# Headers-SolderPads.net
KiCad netlist of a schematic drawn in Altium Designer
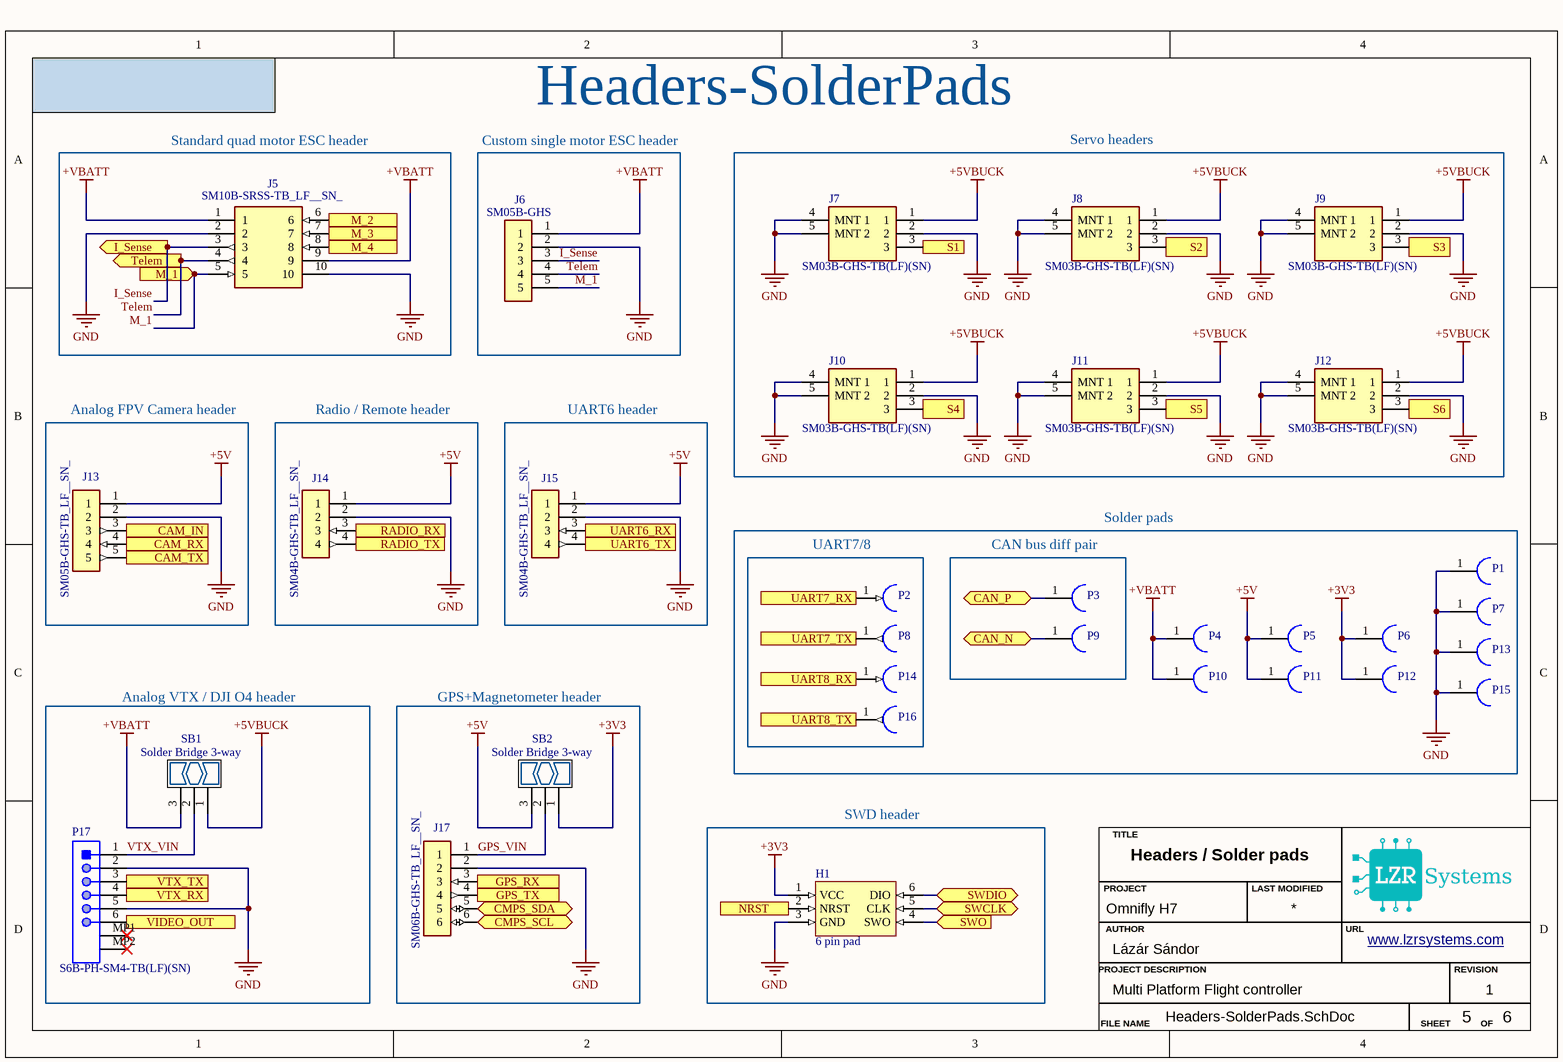
[diagram p0: Headers-SolderPads.SchDoc]

(export (version "E")
  (design (tool "Eeschema 10.0.6"))
  (components
    (comp (ref "H1")
      (value "6 pin pad")
      (footprint "6 pin pad-Footprint-1")
      (libsource (lib "Sandor Lazar") (part "SWD-1.27mm-2x03"))
    )
    (comp (ref "J5")
      (value "SM10B-SRSS-TB_LF__SN_")
      (footprint "SamacSys:SM10B-SRSS-TB")
      (description "Connector")
      (fields
        (field (name "MANUFACTURER_PART_NUMBER") "SM10B-SRSS-TB(LF)(SN)")
        (field (name "MOUSER PART NUMBER") "306-SM10BSRSSTBLFSN")
      )
      (libsource (lib "*") (part "SM10B-SRSS-TB_LF__SN_"))
    )
    (comp (ref "J6")
      (value "SM05B-GHS")
      (footprint "SamacSys:SM05B-GHS-TB")
      (description "Connector")
      (fields (field (name "MANUFACTURER_PART_NUMBER") "SM05B-GHS-TB(LF)(SN)"))
      (libsource (lib "SamacSys") (part "SM05B-GHS-TB_LF__SN_"))
    )
    (comp (ref "J7")
      (value "SM03B-GHS-TB(LF)(SN)")
      (footprint "FP-SM03B-GHS-TB_LF_SN-MFG")
      (description "MCU 32-bit LPC1800 ARM Cortex M3 RISC 1024KB Flash 3.3V 100-Pin TFBGA Tray")
      (libsource (lib "Sandor Lazar") (part "13850a6865a90496d8e6d51657cef87"))
    )
    (comp (ref "J8")
      (value "SM03B-GHS-TB(LF)(SN)")
      (footprint "FP-SM03B-GHS-TB_LF_SN-MFG")
      (description "MCU 32-bit LPC1800 ARM Cortex M3 RISC 1024KB Flash 3.3V 100-Pin TFBGA Tray")
      (libsource (lib "Sandor Lazar") (part "13850a6865a90496d8e6d51657cef87"))
    )
    (comp (ref "J9")
      (value "SM03B-GHS-TB(LF)(SN)")
      (footprint "FP-SM03B-GHS-TB_LF_SN-MFG")
      (description "MCU 32-bit LPC1800 ARM Cortex M3 RISC 1024KB Flash 3.3V 100-Pin TFBGA Tray")
      (libsource (lib "Sandor Lazar") (part "13850a6865a90496d8e6d51657cef87"))
    )
    (comp (ref "J10")
      (value "SM03B-GHS-TB(LF)(SN)")
      (footprint "FP-SM03B-GHS-TB_LF_SN-MFG")
      (description "MCU 32-bit LPC1800 ARM Cortex M3 RISC 1024KB Flash 3.3V 100-Pin TFBGA Tray")
      (libsource (lib "Sandor Lazar") (part "13850a6865a90496d8e6d51657cef87"))
    )
    (comp (ref "J11")
      (value "SM03B-GHS-TB(LF)(SN)")
      (footprint "FP-SM03B-GHS-TB_LF_SN-MFG")
      (description "MCU 32-bit LPC1800 ARM Cortex M3 RISC 1024KB Flash 3.3V 100-Pin TFBGA Tray")
      (libsource (lib "Sandor Lazar") (part "13850a6865a90496d8e6d51657cef87"))
    )
    (comp (ref "J12")
      (value "SM03B-GHS-TB(LF)(SN)")
      (footprint "FP-SM03B-GHS-TB_LF_SN-MFG")
      (description "MCU 32-bit LPC1800 ARM Cortex M3 RISC 1024KB Flash 3.3V 100-Pin TFBGA Tray")
      (libsource (lib "Sandor Lazar") (part "13850a6865a90496d8e6d51657cef87"))
    )
    (comp (ref "J13")
      (value "SM05B-GHS-TB_LF__SN_")
      (footprint "SamacSys:SM05B-GHS-TB")
      (description "Connector")
      (fields (field (name "MANUFACTURER_PART_NUMBER") "SM05B-GHS-TB(LF)(SN)"))
      (libsource (lib "SamacSys") (part "SM05B-GHS-TB_LF__SN_"))
    )
    (comp (ref "J14")
      (value "SM04B-GHS-TB_LF__SN_")
      (footprint "SamacSys:SM04B-GHS-TB")
      (description "Connector")
      (fields (field (name "MANUFACTURER_PART_NUMBER") "SM04B-GHS-TB(LF)(SN)"))
      (libsource (lib "SamacSys") (part "SM04B-GHS-TB_LF__SN_"))
    )
    (comp (ref "J15")
      (value "SM04B-GHS-TB_LF__SN_")
      (footprint "SamacSys:SM04B-GHS-TB")
      (description "Connector")
      (fields (field (name "MANUFACTURER_PART_NUMBER") "SM04B-GHS-TB(LF)(SN)"))
      (libsource (lib "SamacSys") (part "SM04B-GHS-TB_LF__SN_"))
    )
    (comp (ref "J17")
      (value "SM06B-GHS-TB_LF__SN_")
      (footprint "SamacSys:SM06B-GHS-TB")
      (description "Connector")
      (fields (field (name "MANUFACTURER_PART_NUMBER") "SM06B-GHS-TB(LF)(SN)"))
      (libsource (lib "SamacSys") (part "SM06B-GHS-TB_LF__SN_"))
    )
    (comp (ref "P1")
      (value "Solder Pad 2x1.5mm")
      (footprint "Solder Pad 2x1.5mm-Footprint-1")
      (description "Solder Pad 2x1.5mm, 0.5mm hole")
      (libsource (lib "Sandor Lazar") (part "Solder Pad 2x1.5mm"))
    )
    (comp (ref "P2")
      (value "Solder Pad 2x1.5mm")
      (footprint "Solder Pad 2x1.5mm-Footprint-1")
      (description "Solder Pad 2x1.5mm, 0.5mm hole")
      (libsource (lib "Sandor Lazar") (part "Solder Pad 2x1.5mm"))
    )
    (comp (ref "P3")
      (value "Solder Pad 2x1.5mm")
      (footprint "Solder Pad 2x1.5mm-Footprint-1")
      (description "Solder Pad 2x1.5mm, 0.5mm hole")
      (libsource (lib "Sandor Lazar") (part "Solder Pad 2x1.5mm"))
    )
    (comp (ref "P4")
      (value "Solder Pad 2x1.5mm")
      (footprint "Solder Pad 2x1.5mm-Footprint-1")
      (description "Solder Pad 2x1.5mm, 0.5mm hole")
      (libsource (lib "Sandor Lazar") (part "Solder Pad 2x1.5mm"))
    )
    (comp (ref "P5")
      (value "Solder Pad 2x1.5mm")
      (footprint "Solder Pad 2x1.5mm-Footprint-1")
      (description "Solder Pad 2x1.5mm, 0.5mm hole")
      (libsource (lib "Sandor Lazar") (part "Solder Pad 2x1.5mm"))
    )
    (comp (ref "P6")
      (value "Solder Pad 2x1.5mm")
      (footprint "Solder Pad 2x1.5mm-Footprint-1")
      (description "Solder Pad 2x1.5mm, 0.5mm hole")
      (libsource (lib "Sandor Lazar") (part "Solder Pad 2x1.5mm"))
    )
    (comp (ref "P7")
      (value "Solder Pad 2x1.5mm")
      (footprint "Solder Pad 2x1.5mm-Footprint-1")
      (description "Solder Pad 2x1.5mm, 0.5mm hole")
      (libsource (lib "Sandor Lazar") (part "Solder Pad 2x1.5mm"))
    )
    (comp (ref "P8")
      (value "Solder Pad 2x1.5mm")
      (footprint "Solder Pad 2x1.5mm-Footprint-1")
      (description "Solder Pad 2x1.5mm, 0.5mm hole")
      (libsource (lib "Sandor Lazar") (part "Solder Pad 2x1.5mm"))
    )
    (comp (ref "P9")
      (value "Solder Pad 2x1.5mm")
      (footprint "Solder Pad 2x1.5mm-Footprint-1")
      (description "Solder Pad 2x1.5mm, 0.5mm hole")
      (libsource (lib "Sandor Lazar") (part "Solder Pad 2x1.5mm"))
    )
    (comp (ref "P10")
      (value "Solder Pad 2x1.5mm")
      (footprint "Solder Pad 2x1.5mm-Footprint-1")
      (description "Solder Pad 2x1.5mm, 0.5mm hole")
      (libsource (lib "Sandor Lazar") (part "Solder Pad 2x1.5mm"))
    )
    (comp (ref "P11")
      (value "Solder Pad 2x1.5mm")
      (footprint "Solder Pad 2x1.5mm-Footprint-1")
      (description "Solder Pad 2x1.5mm, 0.5mm hole")
      (libsource (lib "Sandor Lazar") (part "Solder Pad 2x1.5mm"))
    )
    (comp (ref "P12")
      (value "Solder Pad 2x1.5mm")
      (footprint "Solder Pad 2x1.5mm-Footprint-1")
      (description "Solder Pad 2x1.5mm, 0.5mm hole")
      (libsource (lib "Sandor Lazar") (part "Solder Pad 2x1.5mm"))
    )
    (comp (ref "P13")
      (value "Solder Pad 2x1.5mm")
      (footprint "Solder Pad 2x1.5mm-Footprint-1")
      (description "Solder Pad 2x1.5mm, 0.5mm hole")
      (libsource (lib "Sandor Lazar") (part "Solder Pad 2x1.5mm"))
    )
    (comp (ref "P14")
      (value "Solder Pad 2x1.5mm")
      (footprint "Solder Pad 2x1.5mm-Footprint-1")
      (description "Solder Pad 2x1.5mm, 0.5mm hole")
      (libsource (lib "Sandor Lazar") (part "Solder Pad 2x1.5mm"))
    )
    (comp (ref "P15")
      (value "Solder Pad 2x1.5mm")
      (footprint "Solder Pad 2x1.5mm-Footprint-1")
      (description "Solder Pad 2x1.5mm, 0.5mm hole")
      (libsource (lib "Sandor Lazar") (part "Solder Pad 2x1.5mm"))
    )
    (comp (ref "P16")
      (value "Solder Pad 2x1.5mm")
      (footprint "Solder Pad 2x1.5mm-Footprint-1")
      (description "Solder Pad 2x1.5mm, 0.5mm hole")
      (libsource (lib "Sandor Lazar") (part "Solder Pad 2x1.5mm"))
    )
    (comp (ref "P17")
      (value "S6B-PH-SM4-TB(LF)(SN)")
      (footprint "JST-S6B-PH-SM4-TB(LF)(SN)_V")
      (description "Connector Header, PH Series, 6 Position, Side Entry, 2.00mm, Solder, Surface Mount, Natural.")
      (libsource (lib "Sandor Lazar") (part "CN-1P-2M-R6"))
    )
    (comp (ref "SB1")
      (value "Solder Bridge 3-way")
      (footprint "Solder Bridge 3-way-Footprint-1")
      (description "3-way solder bridge mainly for power rail selection")
      (libsource (lib "Sandor Lazar") (part "Solder Bridge 3-way"))
    )
    (comp (ref "SB2")
      (value "Solder Bridge 3-way")
      (footprint "Solder Bridge 3-way-Footprint-1")
      (description "3-way solder bridge mainly for power rail selection")
      (libsource (lib "Sandor Lazar") (part "Solder Bridge 3-way"))
    )
  )
  (nets
    (net (code "1") (name "+3V3") (class "Default")
      (node (ref "H1") (pin "1") (pinfunction "VCC_1") (pintype "input"))
      (node (ref "P12") (pin "1") (pinfunction "1_1") (pintype "input"))
      (node (ref "P6") (pin "1") (pinfunction "1_1") (pintype "input"))
      (node (ref "SB2") (pin "1") (pinfunction "1_1") (pintype "passive"))
    )
    (net (code "2") (name "+5V") (class "Default")
      (node (ref "J13") (pin "1") (pinfunction "1_1") (pintype "passive"))
      (node (ref "J14") (pin "1") (pinfunction "1_1") (pintype "passive"))
      (node (ref "J15") (pin "1") (pinfunction "1_1") (pintype "passive"))
      (node (ref "P11") (pin "1") (pinfunction "1_1") (pintype "input"))
      (node (ref "P5") (pin "1") (pinfunction "1_1") (pintype "input"))
      (node (ref "SB2") (pin "3") (pinfunction "3_3") (pintype "passive"))
    )
    (net (code "3") (name "+5VBUCK") (class "Default")
      (node (ref "J10") (pin "1") (pinfunction "1_1") (pintype "passive"))
      (node (ref "J11") (pin "1") (pinfunction "1_1") (pintype "passive"))
      (node (ref "J12") (pin "1") (pinfunction "1_1") (pintype "passive"))
      (node (ref "J7") (pin "1") (pinfunction "1_1") (pintype "passive"))
      (node (ref "J8") (pin "1") (pinfunction "1_1") (pintype "passive"))
      (node (ref "J9") (pin "1") (pinfunction "1_1") (pintype "passive"))
      (node (ref "SB1") (pin "1") (pinfunction "1_1") (pintype "passive"))
    )
    (net (code "4") (name "+VBATT") (class "Default")
      (node (ref "J5") (pin "1") (pinfunction "1_1") (pintype "passive"))
      (node (ref "J5") (pin "9") (pinfunction "9_9") (pintype "passive"))
      (node (ref "J6") (pin "1") (pinfunction "1_1") (pintype "passive"))
      (node (ref "P10") (pin "1") (pinfunction "1_1") (pintype "input"))
      (node (ref "P4") (pin "1") (pinfunction "1_1") (pintype "input"))
      (node (ref "SB1") (pin "3") (pinfunction "3_3") (pintype "passive"))
    )
    (net (code "5") (name "/CAM_IN") (class "Default")
      (node (ref "J13") (pin "3") (pinfunction "3_3") (pintype "output"))
    )
    (net (code "6") (name "/CAM_RX") (class "Default")
      (node (ref "J13") (pin "4") (pinfunction "4_4") (pintype "input"))
    )
    (net (code "7") (name "/CAM_TX") (class "Default")
      (node (ref "J13") (pin "5") (pinfunction "5_5") (pintype "output"))
    )
    (net (code "8") (name "/CAN_N") (class "Default")
      (node (ref "P9") (pin "1") (pinfunction "1_1") (pintype "input"))
    )
    (net (code "9") (name "/CAN_P") (class "Default")
      (node (ref "P3") (pin "1") (pinfunction "1_1") (pintype "input"))
    )
    (net (code "10") (name "/CMPS_SCL") (class "Default")
      (node (ref "J17") (pin "6") (pinfunction "6_6") (pintype "bidirectional"))
    )
    (net (code "11") (name "/CMPS_SDA") (class "Default")
      (node (ref "J17") (pin "5") (pinfunction "5_5") (pintype "bidirectional"))
    )
    (net (code "12") (name "/GPS_RX") (class "Default")
      (node (ref "J17") (pin "3") (pinfunction "3_3") (pintype "input"))
    )
    (net (code "13") (name "/GPS_TX") (class "Default")
      (node (ref "J17") (pin "4") (pinfunction "4_4") (pintype "output"))
    )
    (net (code "14") (name "/GPS_VIN") (class "Default")
      (node (ref "J17") (pin "1") (pinfunction "1_1") (pintype "passive"))
      (node (ref "SB2") (pin "2") (pinfunction "2_2") (pintype "passive"))
    )
    (net (code "15") (name "/I_Sense") (class "Default")
      (node (ref "J5") (pin "3") (pinfunction "3_3") (pintype "output"))
      (node (ref "J6") (pin "3") (pinfunction "3_3") (pintype "output"))
    )
    (net (code "16") (name "/M_1") (class "Default")
      (node (ref "J5") (pin "5") (pinfunction "5_5") (pintype "input"))
      (node (ref "J6") (pin "5") (pinfunction "5_5") (pintype "output"))
    )
    (net (code "17") (name "/M_2") (class "Default")
      (node (ref "J5") (pin "6") (pinfunction "6_6") (pintype "input"))
    )
    (net (code "18") (name "/M_3") (class "Default")
      (node (ref "J5") (pin "7") (pinfunction "7_7") (pintype "input"))
    )
    (net (code "19") (name "/M_4") (class "Default")
      (node (ref "J5") (pin "8") (pinfunction "8_8") (pintype "input"))
    )
    (net (code "20") (name "/NRST") (class "Default")
      (node (ref "H1") (pin "2") (pinfunction "NRST_2") (pintype "input"))
    )
    (net (code "21") (name "/RADIO_RX") (class "Default")
      (node (ref "J14") (pin "3") (pinfunction "3_3") (pintype "input"))
    )
    (net (code "22") (name "/RADIO_TX") (class "Default")
      (node (ref "J14") (pin "4") (pinfunction "4_4") (pintype "output"))
    )
    (net (code "23") (name "/S1") (class "Default")
      (node (ref "J7") (pin "3") (pinfunction "3_3") (pintype "passive"))
    )
    (net (code "24") (name "/S2") (class "Default")
      (node (ref "J8") (pin "3") (pinfunction "3_3") (pintype "passive"))
    )
    (net (code "25") (name "/S3") (class "Default")
      (node (ref "J9") (pin "3") (pinfunction "3_3") (pintype "passive"))
    )
    (net (code "26") (name "/S4") (class "Default")
      (node (ref "J10") (pin "3") (pinfunction "3_3") (pintype "passive"))
    )
    (net (code "27") (name "/S5") (class "Default")
      (node (ref "J11") (pin "3") (pinfunction "3_3") (pintype "passive"))
    )
    (net (code "28") (name "/S6") (class "Default")
      (node (ref "J12") (pin "3") (pinfunction "3_3") (pintype "passive"))
    )
    (net (code "29") (name "/SWCLK") (class "Default")
      (node (ref "H1") (pin "5") (pinfunction "CLK_5") (pintype "input"))
    )
    (net (code "30") (name "/SWDIO") (class "Default")
      (node (ref "H1") (pin "6") (pinfunction "DIO_6") (pintype "input"))
    )
    (net (code "31") (name "/SWO") (class "Default")
      (node (ref "H1") (pin "4") (pinfunction "SWO_4") (pintype "input"))
    )
    (net (code "32") (name "/Telem") (class "Default")
      (node (ref "J5") (pin "4") (pinfunction "4_4") (pintype "output"))
      (node (ref "J6") (pin "4") (pinfunction "4_4") (pintype "input"))
    )
    (net (code "33") (name "/UART6_RX") (class "Default")
      (node (ref "J15") (pin "3") (pinfunction "3_3") (pintype "input"))
    )
    (net (code "34") (name "/UART6_TX") (class "Default")
      (node (ref "J15") (pin "4") (pinfunction "4_4") (pintype "output"))
    )
    (net (code "35") (name "/UART7_RX") (class "Default")
      (node (ref "P2") (pin "1") (pinfunction "1_1") (pintype "input"))
    )
    (net (code "36") (name "/UART7_TX") (class "Default")
      (node (ref "P8") (pin "1") (pinfunction "1_1") (pintype "input"))
    )
    (net (code "37") (name "/UART8_RX") (class "Default")
      (node (ref "P14") (pin "1") (pinfunction "1_1") (pintype "input"))
    )
    (net (code "38") (name "/UART8_TX") (class "Default")
      (node (ref "P16") (pin "1") (pinfunction "1_1") (pintype "input"))
    )
    (net (code "39") (name "/VIDEO_OUT") (class "Default")
      (node (ref "P17") (pin "6") (pinfunction "6_6") (pintype "passive"))
    )
    (net (code "40") (name "/VTX_RX") (class "Default")
      (node (ref "P17") (pin "4") (pinfunction "4_4") (pintype "passive"))
    )
    (net (code "41") (name "/VTX_TX") (class "Default")
      (node (ref "P17") (pin "3") (pinfunction "3_3") (pintype "passive"))
    )
    (net (code "42") (name "/VTX_VIN") (class "Default")
      (node (ref "P17") (pin "1") (pinfunction "1_1") (pintype "passive"))
      (node (ref "SB1") (pin "2") (pinfunction "2_2") (pintype "passive"))
    )
    (net (code "43") (name "GND") (class "Default")
      (node (ref "H1") (pin "3") (pinfunction "GND_3") (pintype "input"))
      (node (ref "J10") (pin "2") (pinfunction "2_2") (pintype "passive"))
      (node (ref "J10") (pin "4") (pinfunction "MNT_1_4") (pintype "passive"))
      (node (ref "J10") (pin "5") (pinfunction "MNT_2_5") (pintype "passive"))
      (node (ref "J11") (pin "2") (pinfunction "2_2") (pintype "passive"))
      (node (ref "J11") (pin "4") (pinfunction "MNT_1_4") (pintype "passive"))
      (node (ref "J11") (pin "5") (pinfunction "MNT_2_5") (pintype "passive"))
      (node (ref "J12") (pin "2") (pinfunction "2_2") (pintype "passive"))
      (node (ref "J12") (pin "4") (pinfunction "MNT_1_4") (pintype "passive"))
      (node (ref "J12") (pin "5") (pinfunction "MNT_2_5") (pintype "passive"))
      (node (ref "J13") (pin "2") (pinfunction "2_2") (pintype "passive"))
      (node (ref "J14") (pin "2") (pinfunction "2_2") (pintype "passive"))
      (node (ref "J15") (pin "2") (pinfunction "2_2") (pintype "passive"))
      (node (ref "J17") (pin "2") (pinfunction "2_2") (pintype "passive"))
      (node (ref "J5") (pin "10") (pinfunction "10_10") (pintype "passive"))
      (node (ref "J5") (pin "2") (pinfunction "2_2") (pintype "passive"))
      (node (ref "J6") (pin "2") (pinfunction "2_2") (pintype "passive"))
      (node (ref "J7") (pin "2") (pinfunction "2_2") (pintype "passive"))
      (node (ref "J7") (pin "4") (pinfunction "MNT_1_4") (pintype "passive"))
      (node (ref "J7") (pin "5") (pinfunction "MNT_2_5") (pintype "passive"))
      (node (ref "J8") (pin "2") (pinfunction "2_2") (pintype "passive"))
      (node (ref "J8") (pin "4") (pinfunction "MNT_1_4") (pintype "passive"))
      (node (ref "J8") (pin "5") (pinfunction "MNT_2_5") (pintype "passive"))
      (node (ref "J9") (pin "2") (pinfunction "2_2") (pintype "passive"))
      (node (ref "J9") (pin "4") (pinfunction "MNT_1_4") (pintype "passive"))
      (node (ref "J9") (pin "5") (pinfunction "MNT_2_5") (pintype "passive"))
      (node (ref "P1") (pin "1") (pinfunction "1_1") (pintype "input"))
      (node (ref "P13") (pin "1") (pinfunction "1_1") (pintype "input"))
      (node (ref "P15") (pin "1") (pinfunction "1_1") (pintype "input"))
      (node (ref "P17") (pin "2") (pinfunction "2_2") (pintype "passive"))
      (node (ref "P17") (pin "5") (pinfunction "5_5") (pintype "passive"))
      (node (ref "P7") (pin "1") (pinfunction "1_1") (pintype "input"))
    )
    (net (code "44") (name "unconnected-(P17-PadMP1)") (class "Default")
      (node (ref "P17") (pin "MP1") (pinfunction "MP1_MP1") (pintype "passive+no_connect"))
    )
    (net (code "45") (name "unconnected-(P17-PadMP2)") (class "Default")
      (node (ref "P17") (pin "MP2") (pinfunction "MP2_MP2") (pintype "passive+no_connect"))
    )
  )
)
